# esp32-thing.net
KiCad netlist of a schematic drawn in EAGLE
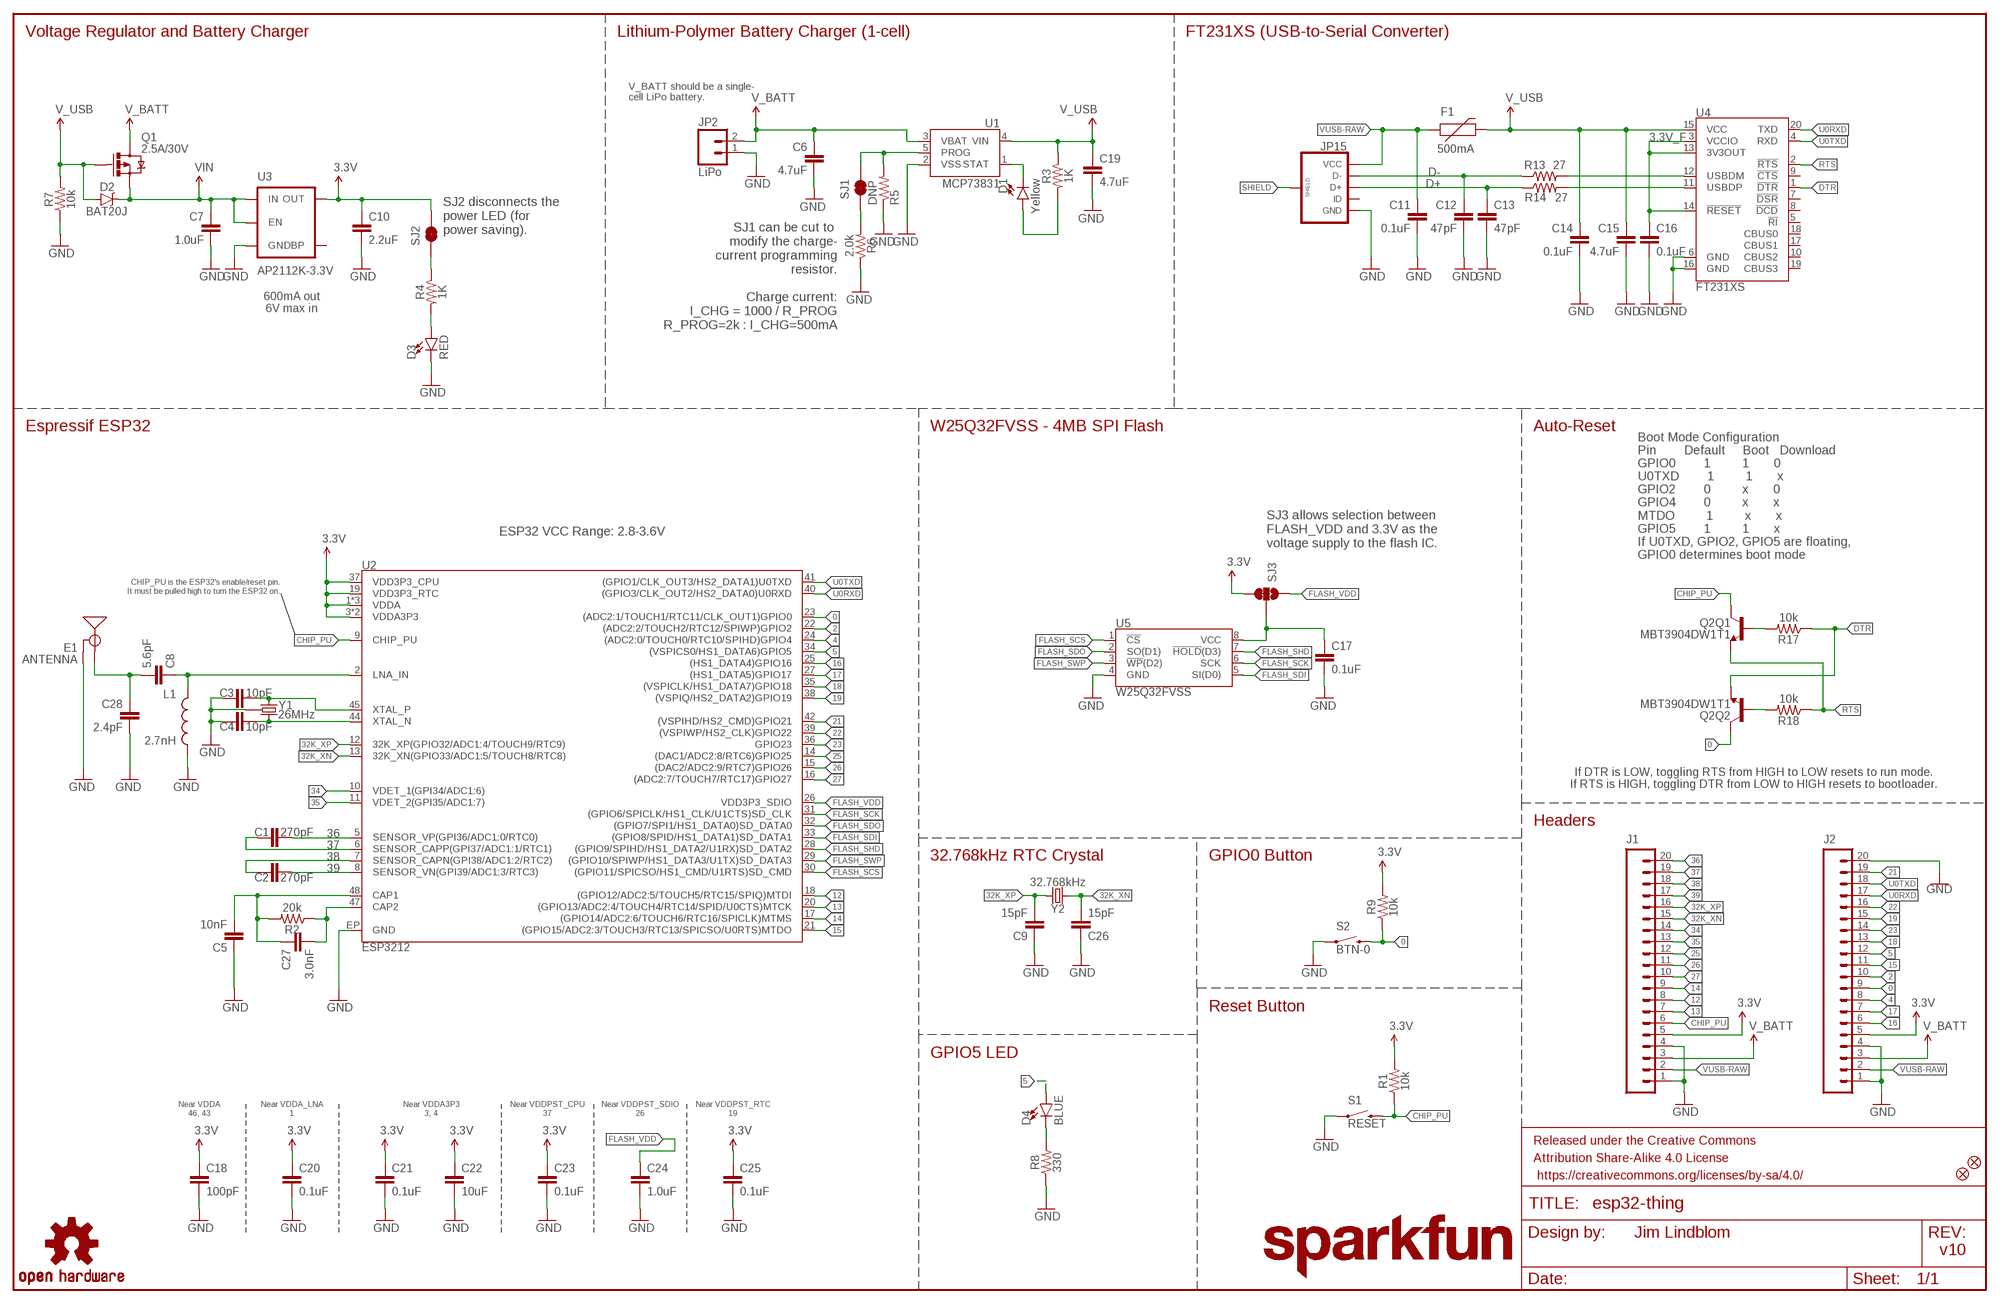
[diagram p0: schematic, sheet 1]

(export (version "E")
  (design (tool "Eeschema 10.0.6"))
  (components
    (comp (ref "C1")
      (value "270pF")
      (footprint "eagle-import:0603")
      (libsource (lib "eagle-import") (part "270PF-50V-5%(0603)"))
    )
    (comp (ref "C2")
      (value "270pF")
      (footprint "eagle-import:0603")
      (libsource (lib "eagle-import") (part "270PF-50V-5%(0603)"))
    )
    (comp (ref "C3")
      (value "10pF")
      (footprint "eagle-import:0603")
      (libsource (lib "eagle-import") (part "10PF-0603-50V-5%"))
    )
    (comp (ref "C4")
      (value "10pF")
      (footprint "eagle-import:0603")
      (libsource (lib "eagle-import") (part "10PF-0603-50V-5%"))
    )
    (comp (ref "C5")
      (value "10nF")
      (footprint "eagle-import:0603")
      (libsource (lib "eagle-import") (part "10NF-0603-50V-10%"))
    )
    (comp (ref "C6")
      (value "4.7uF")
      (footprint "eagle-import:0603")
      (libsource (lib "eagle-import") (part "4.7UF0603"))
    )
    (comp (ref "C7")
      (value "1.0uF")
      (footprint "eagle-import:0805")
      (libsource (lib "eagle-import") (part "1.0UF-0805-25V-(+80/-20%)"))
    )
    (comp (ref "C8")
      (value "5.6pF")
      (footprint "eagle-import:0603")
      (libsource (lib "eagle-import") (part "5.6PF-50V-5%(0603)"))
    )
    (comp (ref "C9")
      (value "15pF")
      (footprint "eagle-import:0603")
      (libsource (lib "eagle-import") (part "15PF-0603-50V-5%"))
    )
    (comp (ref "C10")
      (value "2.2uF")
      (footprint "eagle-import:0603")
      (libsource (lib "eagle-import") (part "2.2UF-0603-10V-20%"))
    )
    (comp (ref "C11")
      (value "0.1uF")
      (footprint "eagle-import:0603")
      (libsource (lib "eagle-import") (part "0.1UF-0603-25V-(+80/-20%)"))
    )
    (comp (ref "C12")
      (value "47pF")
      (footprint "eagle-import:0603")
      (libsource (lib "eagle-import") (part "47PF-0603-50V-5%"))
    )
    (comp (ref "C13")
      (value "47pF")
      (footprint "eagle-import:0603")
      (libsource (lib "eagle-import") (part "47PF-0603-50V-5%"))
    )
    (comp (ref "C14")
      (value "0.1uF")
      (footprint "eagle-import:0603")
      (libsource (lib "eagle-import") (part "0.1UF-0603-25V-(+80/-20%)"))
    )
    (comp (ref "C15")
      (value "4.7uF")
      (footprint "eagle-import:0603-CAP")
      (libsource (lib "eagle-import") (part "4.7UF-6.3V-10%(0603)0603"))
    )
    (comp (ref "C16")
      (value "0.1uF")
      (footprint "eagle-import:0603")
      (libsource (lib "eagle-import") (part "0.1UF-0603-25V-(+80/-20%)"))
    )
    (comp (ref "C17")
      (value "0.1uF")
      (footprint "eagle-import:0603")
      (libsource (lib "eagle-import") (part "0.1UF-0603-25V-(+80/-20%)"))
    )
    (comp (ref "C18")
      (value "100pF")
      (footprint "eagle-import:0603")
      (libsource (lib "eagle-import") (part "100PF-0603-50V-5%"))
    )
    (comp (ref "C19")
      (value "4.7uF")
      (footprint "eagle-import:0603")
      (libsource (lib "eagle-import") (part "4.7UF0603"))
    )
    (comp (ref "C20")
      (value "0.1uF")
      (footprint "eagle-import:0603")
      (libsource (lib "eagle-import") (part "0.1UF-0603-25V-(+80/-20%)"))
    )
    (comp (ref "C21")
      (value "0.1uF")
      (footprint "eagle-import:0603")
      (libsource (lib "eagle-import") (part "0.1UF-0603-25V-(+80/-20%)"))
    )
    (comp (ref "C22")
      (value "10uF")
      (footprint "eagle-import:0603")
      (libsource (lib "eagle-import") (part "10UF-0603-6.3V-20%"))
    )
    (comp (ref "C23")
      (value "0.1uF")
      (footprint "eagle-import:0603")
      (libsource (lib "eagle-import") (part "0.1UF-0603-25V-(+80/-20%)"))
    )
    (comp (ref "C24")
      (value "1.0uF")
      (footprint "eagle-import:0603")
      (libsource (lib "eagle-import") (part "1.0UF-0603-16V-10%"))
    )
    (comp (ref "C25")
      (value "0.1uF")
      (footprint "eagle-import:0603")
      (libsource (lib "eagle-import") (part "0.1UF-0603-25V-(+80/-20%)"))
    )
    (comp (ref "C26")
      (value "15pF")
      (footprint "eagle-import:0603")
      (libsource (lib "eagle-import") (part "15PF-0603-50V-5%"))
    )
    (comp (ref "C27")
      (value "3.0nF")
      (footprint "eagle-import:0603")
      (libsource (lib "eagle-import") (part "3.0NF-0603-50V-5%"))
    )
    (comp (ref "C28")
      (value "2.4pF")
      (footprint "eagle-import:0603")
      (libsource (lib "eagle-import") (part "2.4PF-0603-50V-5%"))
    )
    (comp (ref "D1")
      (value "Yellow")
      (footprint "eagle-import:LED-0603")
      (libsource (lib "eagle-import") (part "LED-YELLOW0603"))
    )
    (comp (ref "D2")
      (value "BAT20J")
      (footprint "eagle-import:SOD-323")
      (libsource (lib "eagle-import") (part "DIODE-SCHOTTKY-BAT20J"))
    )
    (comp (ref "D3")
      (value "RED")
      (footprint "eagle-import:LED-0603")
      (libsource (lib "eagle-import") (part "LED-RED0603"))
    )
    (comp (ref "D4")
      (value "BLUE")
      (footprint "eagle-import:LED-0603")
      (libsource (lib "eagle-import") (part "LED-BLUE0603"))
    )
    (comp (ref "E1")
      (value "ANTENNA")
      (footprint "eagle-import:TRACE_ANTENNA_2.4GHZ_25.7MM_TUNED")
      (libsource (lib "eagle-import") (part "ANTENNATRACE-TUNED"))
    )
    (comp (ref "F1")
      (value "500mA")
      (footprint "eagle-import:PTC-1206")
      (libsource (lib "eagle-import") (part "PTCSMD"))
    )
    (comp (ref "FD1")
      (value "FIDUCIALUFIDUCIAL")
      (footprint "eagle-import:MICRO-FIDUCIAL")
      (libsource (lib "eagle-import") (part "FIDUCIALUFIDUCIAL"))
    )
    (comp (ref "FD2")
      (value "FIDUCIALUFIDUCIAL")
      (footprint "eagle-import:MICRO-FIDUCIAL")
      (libsource (lib "eagle-import") (part "FIDUCIALUFIDUCIAL"))
    )
    (comp (ref "FRAME1")
      (value "FRAME-LEDGER")
      (footprint "eagle-import:CREATIVE_COMMONS")
      (libsource (lib "eagle-import") (part "FRAME-LEDGER"))
    )
    (comp (ref "J1")
      (value "M20NOSILK")
      (footprint "eagle-import:1X20_NOSILK")
      (libsource (lib "eagle-import") (part "M20NOSILK"))
    )
    (comp (ref "J2")
      (value "M20NOSILK")
      (footprint "eagle-import:1X20_NOSILK")
      (libsource (lib "eagle-import") (part "M20NOSILK"))
    )
    (comp (ref "JP2")
      (value "LiPo")
      (footprint "eagle-import:JST-2-PTH")
      (libsource (lib "eagle-import") (part "M02JST-PTH-2"))
    )
    (comp (ref "JP15")
      (value "USB_MICROB_PLUGCONN-11752")
      (footprint "eagle-import:USB-B-MICRO-SMD_V03")
      (libsource (lib "eagle-import") (part "USB_MICROB_PLUGCONN-11752"))
    )
    (comp (ref "L1")
      (value "2.7nH")
      (footprint "eagle-import:0603")
      (libsource (lib "eagle-import") (part "INDUCTOR0603"))
    )
    (comp (ref "LOGO1")
      (value "SFE_LOGO_NAME.2_INCH")
      (footprint "eagle-import:SFE_LOGO_NAME_.2")
      (libsource (lib "eagle-import") (part "SFE_LOGO_NAME.2_INCH"))
    )
    (comp (ref "LOGO2")
      (value "OSHW-LOGOMINI")
      (footprint "eagle-import:OSHW-LOGO-MINI")
      (libsource (lib "eagle-import") (part "OSHW-LOGOMINI"))
    )
    (comp (ref "LOGO3")
      (value "SFE_LOGO_NAME.2_INCH")
      (footprint "eagle-import:SFE_LOGO_NAME_.2")
      (libsource (lib "eagle-import") (part "SFE_LOGO_NAME.2_INCH"))
    )
    (comp (ref "Q1")
      (value "2.5A/30V")
      (footprint "eagle-import:SOT23-3")
      (libsource (lib "eagle-import") (part "MOSFET-PCHANNELDMG2307L"))
    )
    (comp (ref "Q2")
      (value "MBT3904DW1T1")
      (footprint "eagle-import:SC70-6")
      (libsource (lib "eagle-import") (part "MBT3904DW1T1"))
    )
    (comp (ref "R1")
      (value "10k")
      (footprint "eagle-import:0603")
      (libsource (lib "eagle-import") (part "10KOHM-1/10W-1%(0603)0603"))
    )
    (comp (ref "R2")
      (value "20k")
      (footprint "eagle-import:0603")
      (libsource (lib "eagle-import") (part "20KOHM-0603-1/10W-1%"))
    )
    (comp (ref "R3")
      (value "1K")
      (footprint "eagle-import:0603")
      (libsource (lib "eagle-import") (part "1KOHM-1/10W-1%(0603)"))
    )
    (comp (ref "R4")
      (value "1K")
      (footprint "eagle-import:0603")
      (libsource (lib "eagle-import") (part "1KOHM-1/10W-1%(0603)"))
    )
    (comp (ref "R5")
      (value "DNP")
      (footprint "eagle-import:1_6W-RES")
      (libsource (lib "eagle-import") (part "RESISTORPTH-1/6W"))
    )
    (comp (ref "R6")
      (value "2.0k")
      (footprint "eagle-import:0603")
      (libsource (lib "eagle-import") (part "2.0KOHM1/10W5%(0603)"))
    )
    (comp (ref "R7")
      (value "10k")
      (footprint "eagle-import:0603")
      (libsource (lib "eagle-import") (part "10KOHM-0603-1/10W-1%"))
    )
    (comp (ref "R8")
      (value "330")
      (footprint "eagle-import:0603")
      (libsource (lib "eagle-import") (part "330OHM1/10W1%(0603)"))
    )
    (comp (ref "R9")
      (value "10k")
      (footprint "eagle-import:0603")
      (libsource (lib "eagle-import") (part "10KOHM-1/10W-1%(0603)0603"))
    )
    (comp (ref "R13")
      (value "27")
      (footprint "eagle-import:0603")
      (libsource (lib "eagle-import") (part "27OHM1/10W1%(0603)0603-RES"))
    )
    (comp (ref "R14")
      (value "27")
      (footprint "eagle-import:0603")
      (libsource (lib "eagle-import") (part "27OHM1/10W1%(0603)0603-RES"))
    )
    (comp (ref "R17")
      (value "10k")
      (footprint "eagle-import:0603")
      (libsource (lib "eagle-import") (part "10KOHM-0603-1/10W-1%"))
    )
    (comp (ref "R18")
      (value "10k")
      (footprint "eagle-import:0603")
      (libsource (lib "eagle-import") (part "10KOHM-0603-1/10W-1%"))
    )
    (comp (ref "S1")
      (value "RESET")
      (footprint "eagle-import:TACTILE_SWITCH_SMD_4.6X2.8MM")
      (libsource (lib "eagle-import") (part "SWITCH-MOMENTARY-2SMD-4.6X2.8MM"))
    )
    (comp (ref "S2")
      (value "BTN-0")
      (footprint "eagle-import:TACTILE_SWITCH_SMD_4.6X2.8MM")
      (libsource (lib "eagle-import") (part "SWITCH-MOMENTARY-2SMD-4.6X2.8MM"))
    )
    (comp (ref "SJ1")
      (value "JUMPER-PAD-2-NC_BY_TRACE")
      (footprint "eagle-import:PAD-JUMPER-2-NC_BY_TRACE_YES_SILK")
      (libsource (lib "eagle-import") (part "JUMPER-PAD-2-NC_BY_TRACE"))
    )
    (comp (ref "SJ2")
      (value "JUMPER-PAD-2-NC_BY_TRACE")
      (footprint "eagle-import:PAD-JUMPER-2-NC_BY_TRACE_YES_SILK")
      (libsource (lib "eagle-import") (part "JUMPER-PAD-2-NC_BY_TRACE"))
    )
    (comp (ref "SJ3")
      (value "JUMPER-PAD-3-2OF3_NC_BY_TRACE_SMALL")
      (footprint "eagle-import:PAD-JUMPER-3-2OF3_NC_BY_TRACE_YES_SILK_FULL_BOX")
      (libsource (lib "eagle-import") (part "JUMPER-PAD-3-2OF3_NC_BY_TRACE_SMALL"))
    )
    (comp (ref "U1")
      (value "MCP73831")
      (footprint "eagle-import:SOT23-5")
      (libsource (lib "eagle-import") (part "MCP73831"))
    )
    (comp (ref "U2")
      (value "ESP3212")
      (footprint "eagle-import:QFN48-0.4MM")
      (libsource (lib "eagle-import") (part "ESP3212"))
    )
    (comp (ref "U3")
      (value "AP2112K-3.3V")
      (footprint "eagle-import:SOT23-5")
      (libsource (lib "eagle-import") (part "V_REG_LDOSMD"))
    )
    (comp (ref "U4")
      (value "FT231XS")
      (footprint "eagle-import:SSOP20_L")
      (libsource (lib "eagle-import") (part "FT231XS"))
    )
    (comp (ref "U5")
      (value "W25Q32FVSS")
      (footprint "eagle-import:SOIC-8")
      (libsource (lib "eagle-import") (part "W25Q32FVSS"))
    )
    (comp (ref "Y1")
      (value "26MHz")
      (footprint "eagle-import:CRYSTAL-SMD-3.2X2.5")
      (libsource (lib "eagle-import") (part "CRYSTAL-GROUNDED3.2X2.5"))
    )
    (comp (ref "Y2")
      (value "32.768kHz")
      (footprint "eagle-import:CRYSTAL-SMD-3.2X1.5MM")
      (libsource (lib "eagle-import") (part "CRYSTAL-32.768KHZSMD-3.2X1.5"))
    )
  )
  (nets
    (net (code "1") (name "/3.3V_F") (class "Default")
      (node (ref "C16") (pin "1") (pinfunction "1_1") (pintype "passive"))
      (node (ref "U4") (pin "13") (pinfunction "3V3OUT_13") (pintype "bidirectional"))
      (node (ref "U4") (pin "14") (pinfunction "~{RESET}_14") (pintype "bidirectional"))
      (node (ref "U4") (pin "3") (pinfunction "VCCIO_3") (pintype "bidirectional"))
    )
    (net (code "2") (name "/D+") (class "Default")
      (node (ref "C13") (pin "1") (pinfunction "1_1") (pintype "passive"))
      (node (ref "JP15") (pin "D+") (pinfunction "D+_D+") (pintype "bidirectional"))
      (node (ref "R14") (pin "1") (pinfunction "1_1") (pintype "passive"))
    )
    (net (code "3") (name "/D-") (class "Default")
      (node (ref "C12") (pin "1") (pinfunction "1_1") (pintype "passive"))
      (node (ref "JP15") (pin "D-") (pinfunction "D-_D-") (pintype "bidirectional"))
      (node (ref "R13") (pin "1") (pinfunction "1_1") (pintype "passive"))
    )
    (net (code "4") (name "0") (class "Default")
      (node (ref "J2") (pin "9") (pinfunction "9_9") (pintype "passive"))
      (node (ref "Q2") (pin "6") (pinfunction "C_6") (pintype "passive"))
      (node (ref "R9") (pin "1") (pinfunction "1_1") (pintype "passive"))
      (node (ref "S2") (pin "3") (pinfunction "2_3") (pintype "passive"))
      (node (ref "S2") (pin "4") (pinfunction "2_4") (pintype "passive"))
      (node (ref "U2") (pin "23") (pinfunction "(ADC2:1/TOUCH1/RTC11/CLK_OUT1)GPIO0_23") (pintype "bidirectional"))
    )
    (net (code "5") (name "2") (class "Default")
      (node (ref "J2") (pin "10") (pinfunction "10_10") (pintype "passive"))
      (node (ref "U2") (pin "22") (pinfunction "(ADC2:2/TOUCH2/RTC12/SPIWP)GPIO2_22") (pintype "bidirectional"))
    )
    (net (code "6") (name "3.3V") (class "Default")
      (node (ref "C10") (pin "1") (pinfunction "1_1") (pintype "passive"))
      (node (ref "C18") (pin "1") (pinfunction "1_1") (pintype "passive"))
      (node (ref "C20") (pin "1") (pinfunction "1_1") (pintype "passive"))
      (node (ref "C21") (pin "1") (pinfunction "1_1") (pintype "passive"))
      (node (ref "C22") (pin "1") (pinfunction "1_1") (pintype "passive"))
      (node (ref "C23") (pin "1") (pinfunction "1_1") (pintype "passive"))
      (node (ref "C25") (pin "1") (pinfunction "1_1") (pintype "passive"))
      (node (ref "J1") (pin "5") (pinfunction "5_5") (pintype "passive"))
      (node (ref "J2") (pin "5") (pinfunction "5_5") (pintype "passive"))
      (node (ref "R1") (pin "2") (pinfunction "2_2") (pintype "passive"))
      (node (ref "R9") (pin "2") (pinfunction "2_2") (pintype "passive"))
      (node (ref "SJ2") (pin "2") (pinfunction "2_2") (pintype "passive"))
      (node (ref "SJ3") (pin "3") (pinfunction "3_3") (pintype "passive"))
      (node (ref "U2") (pin "1") (pinfunction "VDDA_1") (pintype "bidirectional"))
      (node (ref "U2") (pin "19") (pinfunction "VDD3P3_RTC_19") (pintype "bidirectional"))
      (node (ref "U2") (pin "3") (pinfunction "VDDA3P3_3") (pintype "bidirectional"))
      (node (ref "U2") (pin "37") (pinfunction "VDD3P3_CPU_37") (pintype "bidirectional"))
      (node (ref "U2") (pin "4") (pinfunction "VDDA3P3_4") (pintype "bidirectional"))
      (node (ref "U2") (pin "43") (pinfunction "VDDA_43") (pintype "bidirectional"))
      (node (ref "U2") (pin "46") (pinfunction "VDDA_46") (pintype "bidirectional"))
      (node (ref "U3") (pin "5") (pinfunction "OUT_5") (pintype "passive"))
    )
    (net (code "7") (name "4") (class "Default")
      (node (ref "J2") (pin "8") (pinfunction "8_8") (pintype "passive"))
      (node (ref "U2") (pin "24") (pinfunction "(ADC2:0/TOUCH0/RTC10/SPIHD)GPIO4_24") (pintype "bidirectional"))
    )
    (net (code "8") (name "5") (class "Default")
      (node (ref "D4") (pin "A") (pinfunction "A_A") (pintype "passive"))
      (node (ref "J2") (pin "12") (pinfunction "12_12") (pintype "passive"))
      (node (ref "U2") (pin "34") (pinfunction "(VSPICS0/HS1_DATA6)GPIO5_34") (pintype "bidirectional"))
    )
    (net (code "9") (name "12") (class "Default")
      (node (ref "J1") (pin "8") (pinfunction "8_8") (pintype "passive"))
      (node (ref "U2") (pin "18") (pinfunction "(GPIO12/ADC2:5/TOUCH5/RTC15/SPIQ)MTDI_18") (pintype "bidirectional"))
    )
    (net (code "10") (name "13") (class "Default")
      (node (ref "J1") (pin "7") (pinfunction "7_7") (pintype "passive"))
      (node (ref "U2") (pin "20") (pinfunction "(GPIO13/ADC2:4/TOUCH4/RTC14/SPID/U0CTS)MTCK_20") (pintype "bidirectional"))
    )
    (net (code "11") (name "14") (class "Default")
      (node (ref "J1") (pin "9") (pinfunction "9_9") (pintype "passive"))
      (node (ref "U2") (pin "17") (pinfunction "(GPIO14/ADC2:6/TOUCH6/RTC16/SPICLK)MTMS_17") (pintype "bidirectional"))
    )
    (net (code "12") (name "15") (class "Default")
      (node (ref "J2") (pin "11") (pinfunction "11_11") (pintype "passive"))
      (node (ref "U2") (pin "21") (pinfunction "(GPIO15/ADC2:3/TOUCH3/RTC13/SPICSO/U0RTS)MTDO_21") (pintype "bidirectional"))
    )
    (net (code "13") (name "16") (class "Default")
      (node (ref "J2") (pin "6") (pinfunction "6_6") (pintype "passive"))
      (node (ref "U2") (pin "25") (pinfunction "(HS1_DATA4)GPIO16_25") (pintype "bidirectional"))
    )
    (net (code "14") (name "17") (class "Default")
      (node (ref "J2") (pin "7") (pinfunction "7_7") (pintype "passive"))
      (node (ref "U2") (pin "27") (pinfunction "(HS1_DATA5)GPIO17_27") (pintype "bidirectional"))
    )
    (net (code "15") (name "18") (class "Default")
      (node (ref "J2") (pin "13") (pinfunction "13_13") (pintype "passive"))
      (node (ref "U2") (pin "35") (pinfunction "(VSPICLK/HS1_DATA7)GPIO18_35") (pintype "bidirectional"))
    )
    (net (code "16") (name "19") (class "Default")
      (node (ref "J2") (pin "15") (pinfunction "15_15") (pintype "passive"))
      (node (ref "U2") (pin "38") (pinfunction "(VSPIQ/HS2_DATA2)GPIO19_38") (pintype "bidirectional"))
    )
    (net (code "17") (name "21") (class "Default")
      (node (ref "J2") (pin "19") (pinfunction "19_19") (pintype "passive"))
      (node (ref "U2") (pin "42") (pinfunction "(VSPIHD/HS2_CMD)GPIO21_42") (pintype "bidirectional"))
    )
    (net (code "18") (name "22") (class "Default")
      (node (ref "J2") (pin "16") (pinfunction "16_16") (pintype "passive"))
      (node (ref "U2") (pin "39") (pinfunction "(VSPIWP/HS2_CLK)GPIO22_39") (pintype "bidirectional"))
    )
    (net (code "19") (name "23") (class "Default")
      (node (ref "J2") (pin "14") (pinfunction "14_14") (pintype "passive"))
      (node (ref "U2") (pin "36") (pinfunction "GPIO23_36") (pintype "bidirectional"))
    )
    (net (code "20") (name "25") (class "Default")
      (node (ref "J1") (pin "12") (pinfunction "12_12") (pintype "passive"))
      (node (ref "U2") (pin "14") (pinfunction "(DAC1/ADC2:8/RTC6)GPIO25_14") (pintype "bidirectional"))
    )
    (net (code "21") (name "26") (class "Default")
      (node (ref "J1") (pin "11") (pinfunction "11_11") (pintype "passive"))
      (node (ref "U2") (pin "15") (pinfunction "(DAC2/ADC2:9/RTC7)GPIO26_15") (pintype "bidirectional"))
    )
    (net (code "22") (name "27") (class "Default")
      (node (ref "J1") (pin "10") (pinfunction "10_10") (pintype "passive"))
      (node (ref "U2") (pin "16") (pinfunction "(ADC2:7/TOUCH7/RTC17)GPIO27_16") (pintype "bidirectional"))
    )
    (net (code "23") (name "32K_XN") (class "Default")
      (node (ref "C26") (pin "2") (pinfunction "2_2") (pintype "passive"))
      (node (ref "J1") (pin "15") (pinfunction "15_15") (pintype "passive"))
      (node (ref "U2") (pin "13") (pinfunction "32K_XN(GPIO33/ADC1:5/TOUCH8/RTC8)_13") (pintype "bidirectional"))
      (node (ref "Y2") (pin "P$2") (pinfunction "2_P$2") (pintype "passive"))
    )
    (net (code "24") (name "32K_XP") (class "Default")
      (node (ref "C9") (pin "2") (pinfunction "2_2") (pintype "passive"))
      (node (ref "J1") (pin "16") (pinfunction "16_16") (pintype "passive"))
      (node (ref "U2") (pin "12") (pinfunction "32K_XP(GPIO32/ADC1:4/TOUCH9/RTC9)_12") (pintype "bidirectional"))
      (node (ref "Y2") (pin "P$1") (pinfunction "1_P$1") (pintype "passive"))
    )
    (net (code "25") (name "34") (class "Default")
      (node (ref "J1") (pin "14") (pinfunction "14_14") (pintype "passive"))
      (node (ref "U2") (pin "10") (pinfunction "VDET_1(GPI34/ADC1:6)_10") (pintype "bidirectional"))
    )
    (net (code "26") (name "35") (class "Default")
      (node (ref "J1") (pin "13") (pinfunction "13_13") (pintype "passive"))
      (node (ref "U2") (pin "11") (pinfunction "VDET_2(GPI35/ADC1:7)_11") (pintype "bidirectional"))
    )
    (net (code "27") (name "36") (class "Default")
      (node (ref "C1") (pin "2") (pinfunction "2_2") (pintype "passive"))
      (node (ref "J1") (pin "20") (pinfunction "20_20") (pintype "passive"))
      (node (ref "U2") (pin "5") (pinfunction "SENSOR_VP(GPI36/ADC1:0/RTC0)_5") (pintype "bidirectional"))
    )
    (net (code "28") (name "37") (class "Default")
      (node (ref "C1") (pin "1") (pinfunction "1_1") (pintype "passive"))
      (node (ref "J1") (pin "19") (pinfunction "19_19") (pintype "passive"))
      (node (ref "U2") (pin "6") (pinfunction "SENSOR_CAPP(GPI37/ADC1:1/RTC1)_6") (pintype "bidirectional"))
    )
    (net (code "29") (name "38") (class "Default")
      (node (ref "C2") (pin "1") (pinfunction "1_1") (pintype "passive"))
      (node (ref "J1") (pin "18") (pinfunction "18_18") (pintype "passive"))
      (node (ref "U2") (pin "7") (pinfunction "SENSOR_CAPN(GPI38/ADC1:2/RTC2)_7") (pintype "bidirectional"))
    )
    (net (code "30") (name "39") (class "Default")
      (node (ref "C2") (pin "2") (pinfunction "2_2") (pintype "passive"))
      (node (ref "J1") (pin "17") (pinfunction "17_17") (pintype "passive"))
      (node (ref "U2") (pin "8") (pinfunction "SENSOR_VN(GPI39/ADC1:3/RTC3)_8") (pintype "bidirectional"))
    )
    (net (code "31") (name "CHIP_PU") (class "Default")
      (node (ref "J1") (pin "6") (pinfunction "6_6") (pintype "passive"))
      (node (ref "Q2") (pin "3") (pinfunction "C_3") (pintype "passive"))
      (node (ref "R1") (pin "1") (pinfunction "1_1") (pintype "passive"))
      (node (ref "S1") (pin "3") (pinfunction "2_3") (pintype "passive"))
      (node (ref "S1") (pin "4") (pinfunction "2_4") (pintype "passive"))
      (node (ref "U2") (pin "9") (pinfunction "CHIP_PU_9") (pintype "bidirectional"))
    )
    (net (code "32") (name "DTR") (class "Default")
      (node (ref "Q2") (pin "1") (pinfunction "E_1") (pintype "passive"))
      (node (ref "R17") (pin "1") (pinfunction "1_1") (pintype "passive"))
      (node (ref "U4") (pin "1") (pinfunction "~{DTR}_1") (pintype "bidirectional"))
    )
    (net (code "33") (name "FLASH_SCK") (class "Default")
      (node (ref "U2") (pin "31") (pinfunction "(GPIO6/SPICLK/HS1_CLK/U1CTS)SD_CLK_31") (pintype "bidirectional"))
      (node (ref "U5") (pin "6") (pinfunction "SCK_6") (pintype "bidirectional"))
    )
    (net (code "34") (name "FLASH_SCS") (class "Default")
      (node (ref "U2") (pin "30") (pinfunction "(GPIO11/SPICSO/HS1_CMD/U1RTS)SD_CMD_30") (pintype "bidirectional"))
      (node (ref "U5") (pin "1") (pinfunction "~{CS}_1") (pintype "bidirectional"))
    )
    (net (code "35") (name "FLASH_SDI") (class "Default")
      (node (ref "U2") (pin "33") (pinfunction "(GPIO8/SPID/HS1_DATA1)SD_DATA1_33") (pintype "bidirectional"))
      (node (ref "U5") (pin "5") (pinfunction "SI(D0)_5") (pintype "bidirectional"))
    )
    (net (code "36") (name "FLASH_SDO") (class "Default")
      (node (ref "U2") (pin "32") (pinfunction "(GPIO7/SPI1/HS1_DATA0)SD_DATA0_32") (pintype "bidirectional"))
      (node (ref "U5") (pin "2") (pinfunction "SO(D1)_2") (pintype "bidirectional"))
    )
    (net (code "37") (name "FLASH_SHD") (class "Default")
      (node (ref "U2") (pin "28") (pinfunction "(GPIO9/SPIHD/HS1_DATA2/U1RX)SD_DATA2_28") (pintype "bidirectional"))
      (node (ref "U5") (pin "7") (pinfunction "~{HOLD}(D3)_7") (pintype "bidirectional"))
    )
    (net (code "38") (name "FLASH_SWP") (class "Default")
      (node (ref "U2") (pin "29") (pinfunction "(GPIO10/SPIWP/HS1_DATA3/U1TX)SD_DATA3_29") (pintype "bidirectional"))
      (node (ref "U5") (pin "3") (pinfunction "~{WP}(D2)_3") (pintype "bidirectional"))
    )
    (net (code "39") (name "FLASH_VDD") (class "Default")
      (node (ref "C24") (pin "1") (pinfunction "1_1") (pintype "passive"))
      (node (ref "SJ3") (pin "1") (pinfunction "1_1") (pintype "passive"))
      (node (ref "U2") (pin "26") (pinfunction "VDD3P3_SDIO_26") (pintype "bidirectional"))
    )
    (net (code "40") (name "GND") (class "Default")
      (node (ref "C10") (pin "2") (pinfunction "2_2") (pintype "passive"))
      (node (ref "C11") (pin "2") (pinfunction "2_2") (pintype "passive"))
      (node (ref "C12") (pin "2") (pinfunction "2_2") (pintype "passive"))
      (node (ref "C13") (pin "2") (pinfunction "2_2") (pintype "passive"))
      (node (ref "C14") (pin "2") (pinfunction "2_2") (pintype "passive"))
      (node (ref "C15") (pin "2") (pinfunction "2_2") (pintype "passive"))
      (node (ref "C16") (pin "2") (pinfunction "2_2") (pintype "passive"))
      (node (ref "C17") (pin "2") (pinfunction "2_2") (pintype "passive"))
      (node (ref "C18") (pin "2") (pinfunction "2_2") (pintype "passive"))
      (node (ref "C19") (pin "2") (pinfunction "2_2") (pintype "passive"))
      (node (ref "C20") (pin "2") (pinfunction "2_2") (pintype "passive"))
      (node (ref "C21") (pin "2") (pinfunction "2_2") (pintype "passive"))
      (node (ref "C22") (pin "2") (pinfunction "2_2") (pintype "passive"))
      (node (ref "C23") (pin "2") (pinfunction "2_2") (pintype "passive"))
      (node (ref "C24") (pin "2") (pinfunction "2_2") (pintype "passive"))
      (node (ref "C25") (pin "2") (pinfunction "2_2") (pintype "passive"))
      (node (ref "C26") (pin "1") (pinfunction "1_1") (pintype "passive"))
      (node (ref "C28") (pin "2") (pinfunction "2_2") (pintype "passive"))
      (node (ref "C3") (pin "1") (pinfunction "1_1") (pintype "passive"))
      (node (ref "C4") (pin "1") (pinfunction "1_1") (pintype "passive"))
      (node (ref "C5") (pin "1") (pinfunction "1_1") (pintype "passive"))
      (node (ref "C6") (pin "2") (pinfunction "2_2") (pintype "passive"))
      (node (ref "C7") (pin "2") (pinfunction "2_2") (pintype "passive"))
      (node (ref "C9") (pin "1") (pinfunction "1_1") (pintype "passive"))
      (node (ref "D3") (pin "C") (pinfunction "C_C") (pintype "passive"))
      (node (ref "E1") (pin "GND") (pinfunction "GND_GND") (pintype "bidirectional"))
      (node (ref "E1") (pin "GND2") (pinfunction "GND_GND2") (pintype "bidirectional"))
      (node (ref "J1") (pin "1") (pinfunction "1_1") (pintype "passive"))
      (node (ref "J1") (pin "4") (pinfunction "4_4") (pintype "passive"))
      (node (ref "J2") (pin "1") (pinfunction "1_1") (pintype "passive"))
      (node (ref "J2") (pin "20") (pinfunction "20_20") (pintype "passive"))
      (node (ref "J2") (pin "4") (pinfunction "4_4") (pintype "passive"))
      (node (ref "JP15") (pin "GND") (pinfunction "GND_GND") (pintype "bidirectional"))
      (node (ref "JP2") (pin "1") (pinfunction "1_1") (pintype "passive"))
      (node (ref "L1") (pin "2") (pinfunction "2_2") (pintype "passive"))
      (node (ref "R5") (pin "1") (pinfunction "1_1") (pintype "passive"))
      (node (ref "R6") (pin "1") (pinfunction "1_1") (pintype "passive"))
      (node (ref "R7") (pin "1") (pinfunction "1_1") (pintype "passive"))
      (node (ref "R8") (pin "1") (pinfunction "1_1") (pintype "passive"))
      (node (ref "S1") (pin "1") (pinfunction "1_1") (pintype "passive"))
      (node (ref "S1") (pin "2") (pinfunction "1_2") (pintype "passive"))
      (node (ref "S2") (pin "1") (pinfunction "1_1") (pintype "passive"))
      (node (ref "S2") (pin "2") (pinfunction "1_2") (pintype "passive"))
      (node (ref "U1") (pin "2") (pinfunction "VSS_2") (pintype "power_in"))
      (node (ref "U2") (pin "EP") (pinfunction "GND_EP") (pintype "bidirectional"))
      (node (ref "U3") (pin "2") (pinfunction "GND_2") (pintype "input"))
      (node (ref "U4") (pin "16") (pinfunction "GND_16") (pintype "bidirectional"))
      (node (ref "U4") (pin "6") (pinfunction "GND_6") (pintype "bidirectional"))
      (node (ref "U5") (pin "4") (pinfunction "GND_4") (pintype "bidirectional"))
      (node (ref "Y1") (pin "2") (pinfunction "GND_2") (pintype "passive"))
      (node (ref "Y1") (pin "4") (pinfunction "GND_4") (pintype "passive"))
    )
    (net (code "41") (name "Net-(D1-PadA)") (class "Default")
      (node (ref "D1") (pin "A") (pinfunction "A_A") (pintype "passive"))
      (node (ref "R3") (pin "2") (pinfunction "2_2") (pintype "passive"))
    )
    (net (code "42") (name "Net-(D3-PadA)") (class "Default")
      (node (ref "D3") (pin "A") (pinfunction "A_A") (pintype "passive"))
      (node (ref "R4") (pin "2") (pinfunction "2_2") (pintype "passive"))
    )
    (net (code "43") (name "Net-(D4-PadC)") (class "Default")
      (node (ref "D4") (pin "C") (pinfunction "C_C") (pintype "passive"))
      (node (ref "R8") (pin "2") (pinfunction "2_2") (pintype "passive"))
    )
    (net (code "44") (name "Net-(E1-SIGNAL)") (class "Default")
      (node (ref "C28") (pin "1") (pinfunction "1_1") (pintype "passive"))
      (node (ref "C8") (pin "2") (pinfunction "2_2") (pintype "passive"))
      (node (ref "E1") (pin "ANT") (pinfunction "SIGNAL_ANT") (pintype "bidirectional"))
    )
    (net (code "45") (name "Net-(Q2A-B)") (class "Default")
      (node (ref "Q2") (pin "5") (pinfunction "B_5") (pintype "passive"))
      (node (ref "R17") (pin "2") (pinfunction "2_2") (pintype "passive"))
    )
    (net (code "46") (name "Net-(Q2B-B)") (class "Default")
      (node (ref "Q2") (pin "2") (pinfunction "B_2") (pintype "passive"))
      (node (ref "R18") (pin "2") (pinfunction "2_2") (pintype "passive"))
    )
    (net (code "47") (name "Net-(R4-Pad1)") (class "Default")
      (node (ref "R4") (pin "1") (pinfunction "1_1") (pintype "passive"))
      (node (ref "SJ2") (pin "1") (pinfunction "1_1") (pintype "passive"))
    )
    (net (code "48") (name "Net-(R6-Pad2)") (class "Default")
      (node (ref "R6") (pin "2") (pinfunction "2_2") (pintype "passive"))
      (node (ref "SJ1") (pin "1") (pinfunction "1_1") (pintype "passive"))
    )
    (net (code "49") (name "Net-(U1-PROG)") (class "Default")
      (node (ref "R5") (pin "2") (pinfunction "2_2") (pintype "passive"))
      (node (ref "SJ1") (pin "2") (pinfunction "2_2") (pintype "passive"))
      (node (ref "U1") (pin "5") (pinfunction "PROG_5") (pintype "input"))
    )
    (net (code "50") (name "Net-(U1-STAT)") (class "Default")
      (node (ref "D1") (pin "C") (pinfunction "C_C") (pintype "passive"))
      (node (ref "U1") (pin "1") (pinfunction "STAT_1") (pintype "output"))
    )
    (net (code "51") (name "Net-(U2-CAP1)") (class "Default")
      (node (ref "C27") (pin "1") (pinfunction "1_1") (pintype "passive"))
      (node (ref "C5") (pin "2") (pinfunction "2_2") (pintype "passive"))
      (node (ref "R2") (pin "2") (pinfunction "2_2") (pintype "passive"))
      (node (ref "U2") (pin "48") (pinfunction "CAP1_48") (pintype "bidirectional"))
    )
    (net (code "52") (name "Net-(U2-CAP2)") (class "Default")
      (node (ref "C27") (pin "2") (pinfunction "2_2") (pintype "passive"))
      (node (ref "R2") (pin "1") (pinfunction "1_1") (pintype "passive"))
      (node (ref "U2") (pin "47") (pinfunction "CAP2_47") (pintype "bidirectional"))
    )
    (net (code "53") (name "Net-(U2-LNA_IN)") (class "Default")
      (node (ref "C8") (pin "1") (pinfunction "1_1") (pintype "passive"))
      (node (ref "L1") (pin "1") (pinfunction "1_1") (pintype "passive"))
      (node (ref "U2") (pin "2") (pinfunction "LNA_IN_2") (pintype "bidirectional"))
    )
    (net (code "54") (name "Net-(U2-XTAL_N)") (class "Default")
      (node (ref "C4") (pin "2") (pinfunction "2_2") (pintype "passive"))
      (node (ref "U2") (pin "44") (pinfunction "XTAL_N_44") (pintype "bidirectional"))
      (node (ref "Y1") (pin "3") (pinfunction "2_3") (pintype "passive"))
    )
    (net (code "55") (name "Net-(U2-XTAL_P)") (class "Default")
      (node (ref "C3") (pin "2") (pinfunction "2_2") (pintype "passive"))
      (node (ref "U2") (pin "45") (pinfunction "XTAL_P_45") (pintype "bidirectional"))
      (node (ref "Y1") (pin "1") (pinfunction "1_1") (pintype "passive"))
    )
    (net (code "56") (name "Net-(U4-USBDM)") (class "Default")
      (node (ref "R13") (pin "2") (pinfunction "2_2") (pintype "passive"))
      (node (ref "U4") (pin "12") (pinfunction "USBDM_12") (pintype "bidirectional"))
    )
    (net (code "57") (name "Net-(U4-USBDP)") (class "Default")
      (node (ref "R14") (pin "2") (pinfunction "2_2") (pintype "passive"))
      (node (ref "U4") (pin "11") (pinfunction "USBDP_11") (pintype "bidirectional"))
    )
    (net (code "58") (name "Net-(U5-VCC)") (class "Default")
      (node (ref "C17") (pin "1") (pinfunction "1_1") (pintype "passive"))
      (node (ref "SJ3") (pin "2") (pinfunction "2_2") (pintype "passive"))
      (node (ref "U5") (pin "8") (pinfunction "VCC_8") (pintype "bidirectional"))
    )
    (net (code "59") (name "RTS") (class "Default")
      (node (ref "Q2") (pin "4") (pinfunction "E_4") (pintype "passive"))
      (node (ref "R18") (pin "1") (pinfunction "1_1") (pintype "passive"))
      (node (ref "U4") (pin "2") (pinfunction "~{RTS}_2") (pintype "bidirectional"))
    )
    (net (code "60") (name "SHIELD") (class "Default")
      (node (ref "JP15") (pin "SHIELD1") (pinfunction "SHIELD_SHIELD1") (pintype "bidirectional"))
      (node (ref "JP15") (pin "SHIELD2") (pinfunction "SHIELD_SHIELD2") (pintype "bidirectional"))
      (node (ref "JP15") (pin "SHIELD3") (pinfunction "SHIELD_SHIELD3") (pintype "bidirectional"))
    )
    (net (code "61") (name "U0RXD") (class "Default")
      (node (ref "J2") (pin "17") (pinfunction "17_17") (pintype "passive"))
      (node (ref "U2") (pin "40") (pinfunction "(GPIO3/CLK_OUT2/HS2_DATA0)U0RXD_40") (pintype "bidirectional"))
      (node (ref "U4") (pin "20") (pinfunction "TXD_20") (pintype "bidirectional"))
    )
    (net (code "62") (name "U0TXD") (class "Default")
      (node (ref "J2") (pin "18") (pinfunction "18_18") (pintype "passive"))
      (node (ref "U2") (pin "41") (pinfunction "(GPIO1/CLK_OUT3/HS2_DATA1)U0TXD_41") (pintype "bidirectional"))
      (node (ref "U4") (pin "4") (pinfunction "RXD_4") (pintype "bidirectional"))
    )
    (net (code "63") (name "VIN") (class "Default")
      (node (ref "C7") (pin "1") (pinfunction "1_1") (pintype "passive"))
      (node (ref "D2") (pin "C") (pinfunction "C_C") (pintype "passive"))
      (node (ref "Q1") (pin "2") (pinfunction "S_2") (pintype "passive"))
      (node (ref "U3") (pin "1") (pinfunction "IN_1") (pintype "input"))
      (node (ref "U3") (pin "3") (pinfunction "EN_3") (pintype "input"))
    )
    (net (code "64") (name "VUSB-RAW") (class "Default")
      (node (ref "C11") (pin "1") (pinfunction "1_1") (pintype "passive"))
      (node (ref "F1") (pin "1") (pinfunction "1_1") (pintype "bidirectional"))
      (node (ref "J1") (pin "2") (pinfunction "2_2") (pintype "passive"))
      (node (ref "J2") (pin "2") (pinfunction "2_2") (pintype "passive"))
      (node (ref "JP15") (pin "VBUS") (pinfunction "VCC_VBUS") (pintype "bidirectional"))
    )
    (net (code "65") (name "V_BATT") (class "Default")
      (node (ref "C6") (pin "1") (pinfunction "1_1") (pintype "passive"))
      (node (ref "J1") (pin "3") (pinfunction "3_3") (pintype "passive"))
      (node (ref "J2") (pin "3") (pinfunction "3_3") (pintype "passive"))
      (node (ref "JP2") (pin "2") (pinfunction "2_2") (pintype "passive"))
      (node (ref "Q1") (pin "3") (pinfunction "D_3") (pintype "passive"))
      (node (ref "U1") (pin "3") (pinfunction "VBAT_3") (pintype "power_in"))
    )
    (net (code "66") (name "V_USB") (class "Default")
      (node (ref "C14") (pin "1") (pinfunction "1_1") (pintype "passive"))
      (node (ref "C15") (pin "1") (pinfunction "1_1") (pintype "passive"))
      (node (ref "C19") (pin "1") (pinfunction "1_1") (pintype "passive"))
      (node (ref "D2") (pin "A") (pinfunction "A_A") (pintype "passive"))
      (node (ref "F1") (pin "2") (pinfunction "2_2") (pintype "bidirectional"))
      (node (ref "Q1") (pin "1") (pinfunction "G_1") (pintype "passive"))
      (node (ref "R3") (pin "1") (pinfunction "1_1") (pintype "passive"))
      (node (ref "R7") (pin "2") (pinfunction "2_2") (pintype "passive"))
      (node (ref "U1") (pin "4") (pinfunction "VIN_4") (pintype "power_in"))
      (node (ref "U4") (pin "15") (pinfunction "VCC_15") (pintype "bidirectional"))
    )
    (net (code "67") (name "unconnected-(JP15-PadID)") (class "Default")
      (node (ref "JP15") (pin "ID") (pinfunction "ID_ID") (pintype "bidirectional"))
    )
    (net (code "68") (name "unconnected-(U3-BP-Pad4)") (class "Default")
      (node (ref "U3") (pin "4") (pinfunction "BP_4") (pintype "input"))
    )
    (net (code "69") (name "unconnected-(U4-CBUS0-Pad18)") (class "Default")
      (node (ref "U4") (pin "18") (pinfunction "CBUS0_18") (pintype "bidirectional"))
    )
    (net (code "70") (name "unconnected-(U4-CBUS1-Pad17)") (class "Default")
      (node (ref "U4") (pin "17") (pinfunction "CBUS1_17") (pintype "bidirectional"))
    )
    (net (code "71") (name "unconnected-(U4-CBUS2-Pad10)") (class "Default")
      (node (ref "U4") (pin "10") (pinfunction "CBUS2_10") (pintype "bidirectional"))
    )
    (net (code "72") (name "unconnected-(U4-CBUS3-Pad19)") (class "Default")
      (node (ref "U4") (pin "19") (pinfunction "CBUS3_19") (pintype "bidirectional"))
    )
    (net (code "73") (name "unconnected-(U4-~{CTS}-Pad9)") (class "Default")
      (node (ref "U4") (pin "9") (pinfunction "~{CTS}_9") (pintype "bidirectional"))
    )
    (net (code "74") (name "unconnected-(U4-~{DCD}-Pad8)") (class "Default")
      (node (ref "U4") (pin "8") (pinfunction "~{DCD}_8") (pintype "bidirectional"))
    )
    (net (code "75") (name "unconnected-(U4-~{DSR}-Pad7)") (class "Default")
      (node (ref "U4") (pin "7") (pinfunction "~{DSR}_7") (pintype "bidirectional"))
    )
    (net (code "76") (name "unconnected-(U4-~{RI}-Pad5)") (class "Default")
      (node (ref "U4") (pin "5") (pinfunction "~{RI}_5") (pintype "bidirectional"))
    )
  )
)
